# CCSolenoidDriver.net
KiCad netlist of a schematic drawn in Altium Designer
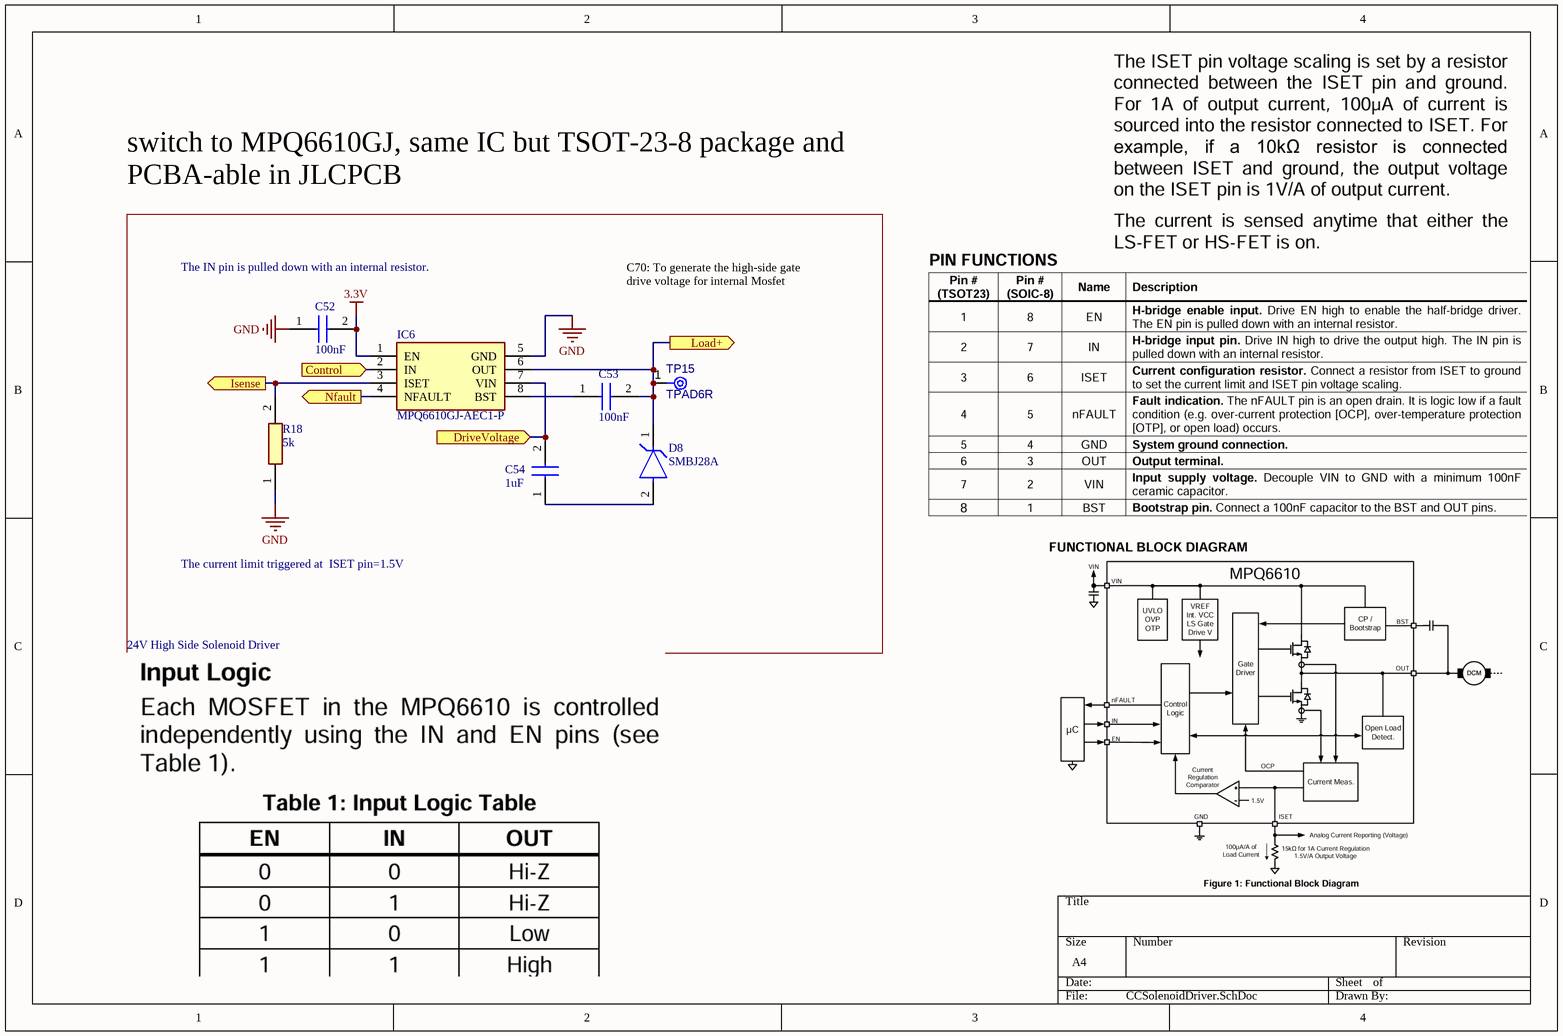
[diagram p0: CCSolenoidDriver.SchDoc]

(export (version "E")
  (design (tool "Eeschema 10.0.6"))
  (components
    (comp (ref "C52")
      (value "100nF")
      (footprint "SamacSys:CAPC1608X90N")
      (description "Capacitor,0603, 50V")
      (fields
        (field (name "MANUFACTURER_PART_NUMBER") "CC0603KRX7R9BB104")
        (field (name "MOUSER PART NUMBER") "603-CC603KRX7R9BB104")
      )
      (libsource (lib "*") (part "CC0603KRX7R9BB104"))
    )
    (comp (ref "C53")
      (value "100nF")
      (footprint "SamacSys:CAPC1608X90N")
      (description "Capacitor,0603, 50V")
      (fields
        (field (name "MANUFACTURER_PART_NUMBER") "CC0603KRX7R9BB104")
        (field (name "MOUSER PART NUMBER") "603-CC603KRX7R9BB104")
      )
      (libsource (lib "*") (part "CC0603KRX7R9BB104"))
    )
    (comp (ref "C54")
      (value "1uF")
      (footprint "SamacSys:CAPC3216X180N")
      (description "1uF,1206, 50v")
      (fields
        (field (name "MANUFACTURER_PART_NUMBER") "CL31B105KBHNNNE")
        (field (name "MOUSER PART NUMBER") "187-CL31B105KBHNNNE")
      )
      (libsource (lib "*") (part "CL31B105KBHNNNE"))
    )
    (comp (ref "D8")
      (value "SMBJ28A")
      (footprint "FP-SMBJ-MFG")
      (description "TVS DIODE 28V 45.4V DO214AA")
      (fields
        (field (name "MANUFACTURER") "Littelfuse Inc")
        (field (name "OCTOPART") "https://octopart.com/smbj28a-littelfuse-350790")
      )
      (libsource (lib "Altium Content Vault") (part "f813f71cba58e380607f5dd3caf9714"))
    )
    (comp (ref "IC6")
      (value "MPQ6610GJ-AEC1-P")
      (footprint "SOT65P280X100-8N")
      (description "Integrated Circuit")
      (libsource (lib "Yuxuan chen") (part "MPQ6610GJ-AEC1-P"))
    )
    (comp (ref "R18")
      (value "5k")
      (footprint "SamacSys:RESC1608X55N")
      (description "0603 5K resistor, Pick based component in JLCPCB lib")
      (fields (field (name "MANUFACTURER_PART_NUMBER") "0603WAF5101T5E"))
      (libsource (lib "*") (part "0603WAF5101T5E"))
    )
    (comp (ref "TP15")
      (value "TPAD6R")
      (footprint "TP06R")
      (description "0.6mm round")
      (libsource (lib "Yuxuan chen") (part "CMP-001-0001-4"))
    )
  )
  (nets
    (net (code "1") (name "/Control") (class "Default")
      (node (ref "IC6") (pin "2") (pinfunction "IN_2") (pintype "passive"))
    )
    (net (code "2") (name "/DriveVoltage") (class "Default")
      (node (ref "C54") (pin "2") (pinfunction "2_2") (pintype "passive"))
      (node (ref "IC6") (pin "7") (pinfunction "VIN_7") (pintype "passive"))
    )
    (net (code "3") (name "/Isense") (class "Default")
      (node (ref "IC6") (pin "3") (pinfunction "ISET_3") (pintype "passive"))
      (node (ref "R18") (pin "2") (pinfunction "2_2") (pintype "passive"))
    )
    (net (code "4") (name "/Load+") (class "Default")
      (node (ref "C53") (pin "2") (pinfunction "2_2") (pintype "passive"))
      (node (ref "D8") (pin "1") (pinfunction "C_1") (pintype "passive"))
      (node (ref "IC6") (pin "6") (pinfunction "OUT_6") (pintype "passive"))
      (node (ref "TP15") (pin "1") (pinfunction "TP_1") (pintype "passive"))
    )
    (net (code "5") (name "/Nfault") (class "Default")
      (node (ref "IC6") (pin "4") (pinfunction "NFAULT_4") (pintype "passive"))
    )
    (net (code "6") (name "3.3V") (class "Default")
      (node (ref "C52") (pin "2") (pinfunction "2_2") (pintype "passive"))
      (node (ref "IC6") (pin "1") (pinfunction "EN_1") (pintype "passive"))
    )
    (net (code "7") (name "GND") (class "Default")
      (node (ref "C52") (pin "1") (pinfunction "1_1") (pintype "passive"))
      (node (ref "IC6") (pin "5") (pinfunction "GND_5") (pintype "passive"))
      (node (ref "R18") (pin "1") (pinfunction "1_1") (pintype "passive"))
    )
    (net (code "8") (name "Net-(D8-A)") (class "Default")
      (node (ref "C54") (pin "1") (pinfunction "1_1") (pintype "passive"))
      (node (ref "D8") (pin "2") (pinfunction "A_2") (pintype "passive"))
    )
    (net (code "9") (name "Net-(IC6-BST)") (class "Default")
      (node (ref "C53") (pin "1") (pinfunction "1_1") (pintype "passive"))
      (node (ref "IC6") (pin "8") (pinfunction "BST_8") (pintype "passive"))
    )
  )
)
